# NeatoLDS_Breakout_Board_v1_1.net
KiCad netlist of a schematic drawn in EAGLE
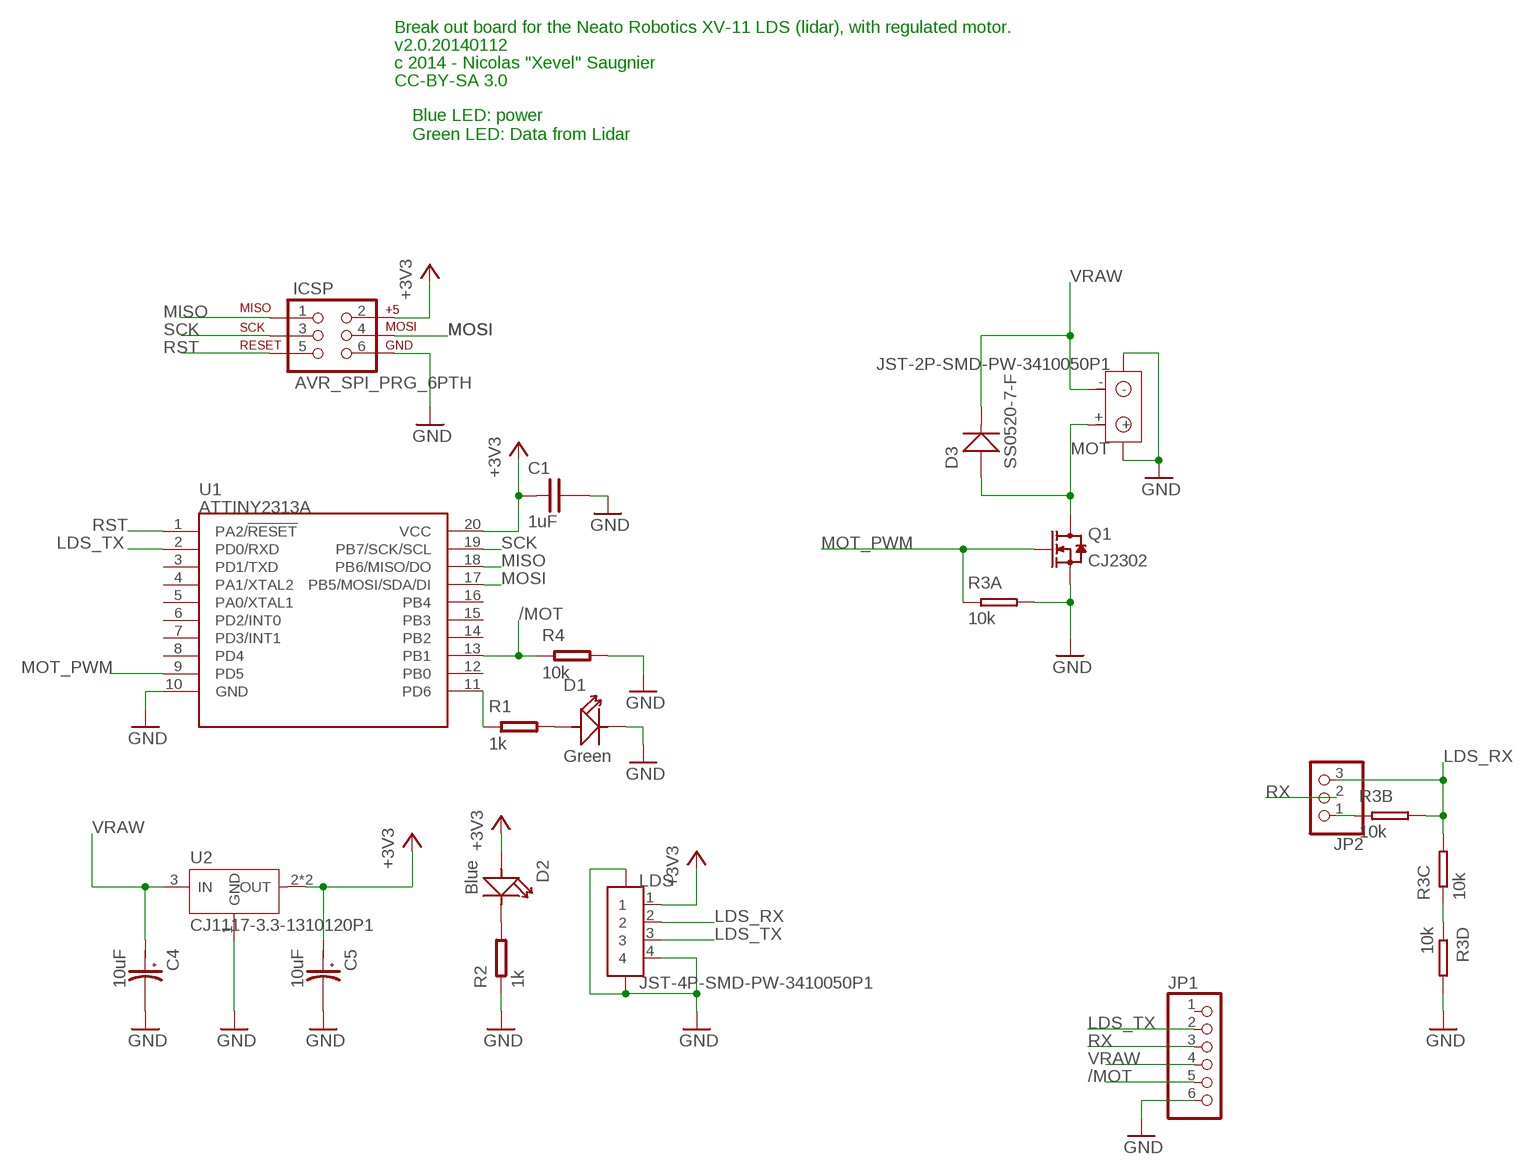
[diagram p0: schematic, sheet 1]

(export (version "E")
  (design (tool "Eeschema 10.0.6"))
  (components
    (comp (ref "C1")
      (value "1uF")
      (footprint "eagle-import:C0603")
      (libsource (lib "eagle-import") (part "C-0603"))
    )
    (comp (ref "C4")
      (value "10uF")
      (footprint "eagle-import:AVX-A")
      (libsource (lib "eagle-import") (part "C-POLAR-A"))
    )
    (comp (ref "C5")
      (value "10uF")
      (footprint "eagle-import:AVX-A")
      (libsource (lib "eagle-import") (part "C-POLAR-A"))
    )
    (comp (ref "D1")
      (value "Green")
      (footprint "eagle-import:LED0603")
      (libsource (lib "eagle-import") (part "LED"))
    )
    (comp (ref "D2")
      (value "Blue")
      (footprint "eagle-import:LED0603")
      (libsource (lib "eagle-import") (part "LED"))
    )
    (comp (ref "D3")
      (value "SS0520-7-F")
      (footprint "eagle-import:SOD123")
      (libsource (lib "eagle-import") (part "D-SOD-123"))
    )
    (comp (ref "ICSP")
      (value "AVR_SPI_PRG_6PTH")
      (footprint "eagle-import:2X3")
      (libsource (lib "eagle-import") (part "AVR_SPI_PRG_6PTH"))
    )
    (comp (ref "JP1")
      (value "PINHD-1X6")
      (footprint "eagle-import:1X06")
      (libsource (lib "eagle-import") (part "PINHD-1X6"))
    )
    (comp (ref "JP2")
      (value "PINHD-1X3")
      (footprint "eagle-import:1X03")
      (libsource (lib "eagle-import") (part "PINHD-1X3"))
    )
    (comp (ref "LDS")
      (value "JST-4P-SMD-PW-3410050P1")
      (footprint "eagle-import:CON-4P-SMD-2.0-90D")
      (libsource (lib "eagle-import") (part "JST-4P-SMD-PW-3410050P1"))
    )
    (comp (ref "MOT")
      (value "JST-2P-SMD-PW-3410050P1")
      (footprint "eagle-import:2P-SMD-2.0-90D")
      (libsource (lib "eagle-import") (part "JST-2P-SMD-PW-3410050P1"))
    )
    (comp (ref "Q1")
      (value "CJ2302")
      (footprint "eagle-import:SOT23")
      (libsource (lib "eagle-import") (part "MOSFET-N-044020001"))
    )
    (comp (ref "R1")
      (value "1k")
      (footprint "eagle-import:R0603")
      (libsource (lib "eagle-import") (part "R-0603"))
    )
    (comp (ref "R2")
      (value "1k")
      (footprint "eagle-import:R0603")
      (libsource (lib "eagle-import") (part "R-0603"))
    )
    (comp (ref "R3")
      (value "10k")
      (footprint "eagle-import:R1206-8")
      (libsource (lib "eagle-import") (part "R-4R"))
    )
    (comp (ref "R4")
      (value "10k")
      (footprint "eagle-import:R0603")
      (libsource (lib "eagle-import") (part "R-0603"))
    )
    (comp (ref "U1")
      (value "ATTINY2313A")
      (footprint "eagle-import:SOP20W")
      (libsource (lib "eagle-import") (part "ATTINY2313A"))
    )
    (comp (ref "U2")
      (value "CJ1117-3.3-1310120P1")
      (footprint "eagle-import:SOT89")
      (libsource (lib "eagle-import") (part "CJ1117-3.3-1310120P1"))
    )
  )
  (nets
    (net (code "1") (name "+3V3") (class "Default")
      (node (ref "C1") (pin "1") (pinfunction "1_1") (pintype "passive"))
      (node (ref "C5") (pin "+") (pinfunction "1_+") (pintype "bidirectional"))
      (node (ref "D2") (pin "+") (pinfunction "+_+") (pintype "passive"))
      (node (ref "ICSP") (pin "2") (pinfunction "2_2") (pintype "passive"))
      (node (ref "LDS") (pin "1") (pinfunction "1_1") (pintype "bidirectional"))
      (node (ref "U1") (pin "20") (pinfunction "VCC_20") (pintype "bidirectional"))
      (node (ref "U2") (pin "2") (pinfunction "OUT_2") (pintype "bidirectional"))
      (node (ref "U2") (pin "4") (pinfunction "OUT_4") (pintype "bidirectional"))
    )
    (net (code "2") (name "/LDS_RX") (class "Default")
      (node (ref "JP2") (pin "3") (pinfunction "3_3") (pintype "passive"))
      (node (ref "LDS") (pin "2") (pinfunction "2_2") (pintype "bidirectional"))
      (node (ref "R3") (pin "6") (pinfunction "2_6") (pintype "passive"))
      (node (ref "R3") (pin "7") (pinfunction "2_7") (pintype "passive"))
    )
    (net (code "3") (name "/LDS_TX") (class "Default")
      (node (ref "JP1") (pin "2") (pinfunction "2_2") (pintype "passive"))
      (node (ref "LDS") (pin "3") (pinfunction "3_3") (pintype "bidirectional"))
      (node (ref "U1") (pin "2") (pinfunction "PD0/RXD_2") (pintype "bidirectional"))
    )
    (net (code "4") (name "/MISO") (class "Default")
      (node (ref "ICSP") (pin "1") (pinfunction "1_1") (pintype "passive"))
      (node (ref "U1") (pin "18") (pinfunction "PB6/MISO/DO_18") (pintype "bidirectional"))
    )
    (net (code "5") (name "/MOSI") (class "Default")
      (node (ref "ICSP") (pin "4") (pinfunction "4_4") (pintype "passive"))
      (node (ref "U1") (pin "17") (pinfunction "PB5/MOSI/SDA/DI_17") (pintype "bidirectional"))
    )
    (net (code "6") (name "/MOT_PWM") (class "Default")
      (node (ref "Q1") (pin "1") (pinfunction "G_1") (pintype "passive"))
      (node (ref "R3") (pin "1") (pinfunction "1_1") (pintype "passive"))
      (node (ref "U1") (pin "9") (pinfunction "PD5_9") (pintype "bidirectional"))
    )
    (net (code "7") (name "/RST") (class "Default")
      (node (ref "ICSP") (pin "5") (pinfunction "5_5") (pintype "passive"))
      (node (ref "U1") (pin "1") (pinfunction "PA2/~{RESET}_1") (pintype "bidirectional"))
    )
    (net (code "8") (name "/RX") (class "Default")
      (node (ref "JP1") (pin "3") (pinfunction "3_3") (pintype "passive"))
      (node (ref "JP2") (pin "2") (pinfunction "2_2") (pintype "passive"))
    )
    (net (code "9") (name "/SCK") (class "Default")
      (node (ref "ICSP") (pin "3") (pinfunction "3_3") (pintype "passive"))
      (node (ref "U1") (pin "19") (pinfunction "PB7/SCK/SCL_19") (pintype "bidirectional"))
    )
    (net (code "10") (name "/VRAW") (class "Default")
      (node (ref "C4") (pin "+") (pinfunction "1_+") (pintype "bidirectional"))
      (node (ref "D3") (pin "-") (pinfunction "-_-") (pintype "passive"))
      (node (ref "JP1") (pin "4") (pinfunction "4_4") (pintype "passive"))
      (node (ref "MOT") (pin "-") (pinfunction "-_-") (pintype "bidirectional"))
      (node (ref "U2") (pin "3") (pinfunction "IN_3") (pintype "bidirectional"))
    )
    (net (code "11") (name "/{slash}MOT") (class "Default")
      (node (ref "JP1") (pin "5") (pinfunction "5_5") (pintype "passive"))
      (node (ref "R4") (pin "1") (pinfunction "1_1") (pintype "passive"))
      (node (ref "U1") (pin "13") (pinfunction "PB1_13") (pintype "bidirectional"))
    )
    (net (code "12") (name "GND") (class "Default")
      (node (ref "C1") (pin "2") (pinfunction "2_2") (pintype "passive"))
      (node (ref "C4") (pin "-") (pinfunction "2_-") (pintype "bidirectional"))
      (node (ref "C5") (pin "-") (pinfunction "2_-") (pintype "bidirectional"))
      (node (ref "D1") (pin "-") (pinfunction "-_-") (pintype "passive"))
      (node (ref "ICSP") (pin "6") (pinfunction "6_6") (pintype "passive"))
      (node (ref "JP1") (pin "6") (pinfunction "6_6") (pintype "passive"))
      (node (ref "LDS") (pin "4") (pinfunction "4_4") (pintype "bidirectional"))
      (node (ref "LDS") (pin "5") (pinfunction "5_5") (pintype "bidirectional"))
      (node (ref "LDS") (pin "6") (pinfunction "6_6") (pintype "bidirectional"))
      (node (ref "MOT") (pin "3") (pinfunction "3_3") (pintype "bidirectional"))
      (node (ref "MOT") (pin "4") (pinfunction "4_4") (pintype "bidirectional"))
      (node (ref "Q1") (pin "2") (pinfunction "S_2") (pintype "passive"))
      (node (ref "R2") (pin "1") (pinfunction "1_1") (pintype "passive"))
      (node (ref "R3") (pin "5") (pinfunction "2_5") (pintype "passive"))
      (node (ref "R3") (pin "8") (pinfunction "2_8") (pintype "passive"))
      (node (ref "R4") (pin "2") (pinfunction "2_2") (pintype "passive"))
      (node (ref "U1") (pin "10") (pinfunction "GND_10") (pintype "bidirectional"))
      (node (ref "U2") (pin "1") (pinfunction "GND_1") (pintype "bidirectional"))
    )
    (net (code "13") (name "Net-(D1-Pad+)") (class "Default")
      (node (ref "D1") (pin "+") (pinfunction "+_+") (pintype "passive"))
      (node (ref "R1") (pin "2") (pinfunction "2_2") (pintype "passive"))
    )
    (net (code "14") (name "Net-(D2-Pad-)") (class "Default")
      (node (ref "D2") (pin "-") (pinfunction "-_-") (pintype "passive"))
      (node (ref "R2") (pin "2") (pinfunction "2_2") (pintype "passive"))
    )
    (net (code "15") (name "Net-(Q1-D)") (class "Default")
      (node (ref "D3") (pin "+") (pinfunction "+_+") (pintype "passive"))
      (node (ref "MOT") (pin "+") (pinfunction "+_+") (pintype "bidirectional"))
      (node (ref "Q1") (pin "3") (pinfunction "D_3") (pintype "passive"))
    )
    (net (code "16") (name "Net-(R3B-1)") (class "Default")
      (node (ref "JP2") (pin "1") (pinfunction "1_1") (pintype "passive"))
      (node (ref "R3") (pin "2") (pinfunction "1_2") (pintype "passive"))
    )
    (net (code "17") (name "Net-(R3C-1)") (class "Default")
      (node (ref "R3") (pin "3") (pinfunction "1_3") (pintype "passive"))
      (node (ref "R3") (pin "4") (pinfunction "1_4") (pintype "passive"))
    )
    (net (code "18") (name "Net-(U1-PD6)") (class "Default")
      (node (ref "R1") (pin "1") (pinfunction "1_1") (pintype "passive"))
      (node (ref "U1") (pin "11") (pinfunction "PD6_11") (pintype "bidirectional"))
    )
    (net (code "19") (name "unconnected-(JP1-Pad1)") (class "Default")
      (node (ref "JP1") (pin "1") (pinfunction "1_1") (pintype "passive"))
    )
    (net (code "20") (name "unconnected-(U1-PA0{slash}XTAL1-Pad5)") (class "Default")
      (node (ref "U1") (pin "5") (pinfunction "PA0/XTAL1_5") (pintype "bidirectional"))
    )
    (net (code "21") (name "unconnected-(U1-PA1{slash}XTAL2-Pad4)") (class "Default")
      (node (ref "U1") (pin "4") (pinfunction "PA1/XTAL2_4") (pintype "bidirectional"))
    )
    (net (code "22") (name "unconnected-(U1-PB0-Pad12)") (class "Default")
      (node (ref "U1") (pin "12") (pinfunction "PB0_12") (pintype "bidirectional"))
    )
    (net (code "23") (name "unconnected-(U1-PB2-Pad14)") (class "Default")
      (node (ref "U1") (pin "14") (pinfunction "PB2_14") (pintype "bidirectional"))
    )
    (net (code "24") (name "unconnected-(U1-PB3-Pad15)") (class "Default")
      (node (ref "U1") (pin "15") (pinfunction "PB3_15") (pintype "bidirectional"))
    )
    (net (code "25") (name "unconnected-(U1-PB4-Pad16)") (class "Default")
      (node (ref "U1") (pin "16") (pinfunction "PB4_16") (pintype "bidirectional"))
    )
    (net (code "26") (name "unconnected-(U1-PD1{slash}TXD-Pad3)") (class "Default")
      (node (ref "U1") (pin "3") (pinfunction "PD1/TXD_3") (pintype "bidirectional"))
    )
    (net (code "27") (name "unconnected-(U1-PD2{slash}INT0-Pad6)") (class "Default")
      (node (ref "U1") (pin "6") (pinfunction "PD2/INT0_6") (pintype "bidirectional"))
    )
    (net (code "28") (name "unconnected-(U1-PD3{slash}INT1-Pad7)") (class "Default")
      (node (ref "U1") (pin "7") (pinfunction "PD3/INT1_7") (pintype "bidirectional"))
    )
    (net (code "29") (name "unconnected-(U1-PD4-Pad8)") (class "Default")
      (node (ref "U1") (pin "8") (pinfunction "PD4_8") (pintype "bidirectional"))
    )
  )
)
